# MouseGoggles_HatBrd-1-0.net
KiCad netlist of a schematic drawn in EAGLE
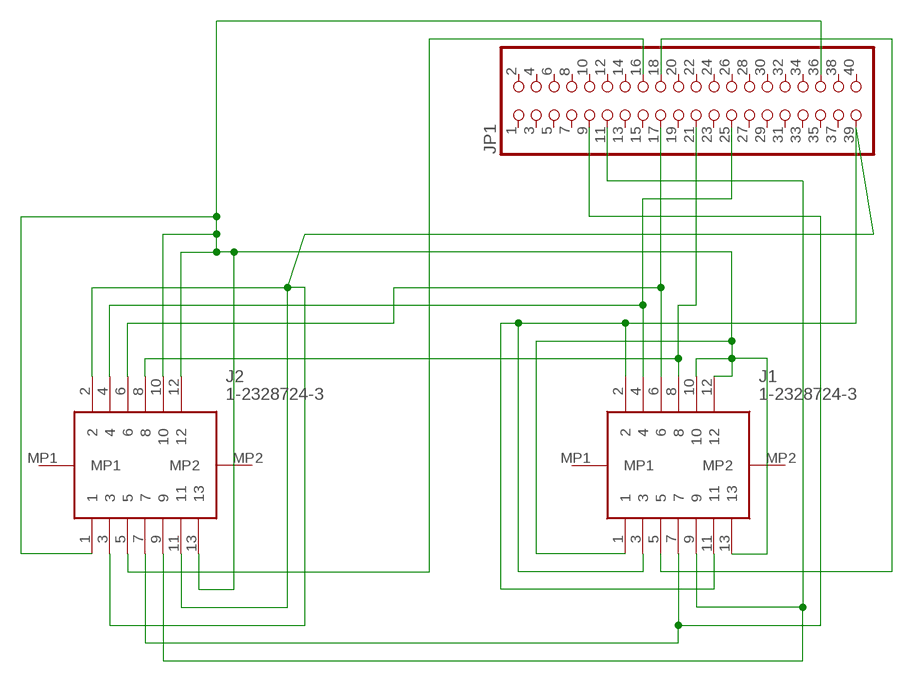
[diagram p0: schematic, sheet 1]

(export (version "E")
  (design (tool "Eeschema 10.0.6"))
  (components
    (comp (ref "J1")
      (value "1-2328724-3")
      (footprint "eagle-import:123287243")
      (fields (field (name "MOUSER_PART_NUMBER") "571-1-2328724-3"))
      (libsource (lib "eagle-import") (part "1-2328724-3"))
    )
    (comp (ref "J2")
      (value "1-2328724-3")
      (footprint "eagle-import:123287243")
      (fields (field (name "MOUSER_PART_NUMBER") "571-1-2328724-3"))
      (libsource (lib "eagle-import") (part "1-2328724-3"))
    )
    (comp (ref "JP1")
      (value "PINHD-2X20-BIG")
      (footprint "eagle-import:2X20-BIG")
      (libsource (lib "eagle-import") (part "PINHD-2X20-BIG"))
    )
  )
  (nets
    (net (code "1") (name "Net-(J1-Pad1)") (class "Default")
      (node (ref "J1") (pin "1") (pinfunction "1_1") (pintype "bidirectional"))
      (node (ref "J1") (pin "10") (pinfunction "10_10") (pintype "bidirectional"))
      (node (ref "J1") (pin "12") (pinfunction "12_12") (pintype "bidirectional"))
      (node (ref "J1") (pin "13") (pinfunction "13_13") (pintype "bidirectional"))
      (node (ref "J2") (pin "1") (pinfunction "1_1") (pintype "bidirectional"))
      (node (ref "J2") (pin "10") (pinfunction "10_10") (pintype "bidirectional"))
      (node (ref "J2") (pin "12") (pinfunction "12_12") (pintype "bidirectional"))
      (node (ref "J2") (pin "13") (pinfunction "13_13") (pintype "bidirectional"))
      (node (ref "JP1") (pin "36") (pinfunction "36_36") (pintype "passive"))
    )
    (net (code "2") (name "Net-(J1-Pad4)") (class "Default")
      (node (ref "J1") (pin "4") (pinfunction "4_4") (pintype "bidirectional"))
      (node (ref "J2") (pin "4") (pinfunction "4_4") (pintype "bidirectional"))
      (node (ref "JP1") (pin "25") (pinfunction "25_25") (pintype "passive"))
    )
    (net (code "3") (name "Net-(J1-Pad5)") (class "Default")
      (node (ref "J1") (pin "5") (pinfunction "5_5") (pintype "bidirectional"))
      (node (ref "JP1") (pin "18") (pinfunction "18_18") (pintype "passive"))
    )
    (net (code "4") (name "Net-(J1-Pad6)") (class "Default")
      (node (ref "J1") (pin "6") (pinfunction "6_6") (pintype "bidirectional"))
      (node (ref "J2") (pin "6") (pinfunction "6_6") (pintype "bidirectional"))
      (node (ref "JP1") (pin "17") (pinfunction "17_17") (pintype "passive"))
    )
    (net (code "5") (name "Net-(J1-Pad7)") (class "Default")
      (node (ref "J1") (pin "7") (pinfunction "7_7") (pintype "bidirectional"))
      (node (ref "J2") (pin "7") (pinfunction "7_7") (pintype "bidirectional"))
      (node (ref "JP1") (pin "9") (pinfunction "9_9") (pintype "passive"))
    )
    (net (code "6") (name "Net-(J1-Pad8)") (class "Default")
      (node (ref "J1") (pin "8") (pinfunction "8_8") (pintype "bidirectional"))
      (node (ref "J2") (pin "8") (pinfunction "8_8") (pintype "bidirectional"))
      (node (ref "JP1") (pin "21") (pinfunction "21_21") (pintype "passive"))
    )
    (net (code "7") (name "Net-(J1-Pad9)") (class "Default")
      (node (ref "J1") (pin "9") (pinfunction "9_9") (pintype "bidirectional"))
      (node (ref "J2") (pin "9") (pinfunction "9_9") (pintype "bidirectional"))
      (node (ref "JP1") (pin "11") (pinfunction "11_11") (pintype "passive"))
    )
    (net (code "8") (name "Net-(J1-Pad11)") (class "Default")
      (node (ref "J1") (pin "11") (pinfunction "11_11") (pintype "bidirectional"))
      (node (ref "J1") (pin "2") (pinfunction "2_2") (pintype "bidirectional"))
      (node (ref "J1") (pin "3") (pinfunction "3_3") (pintype "bidirectional"))
      (node (ref "J2") (pin "11") (pinfunction "11_11") (pintype "bidirectional"))
      (node (ref "J2") (pin "2") (pinfunction "2_2") (pintype "bidirectional"))
      (node (ref "J2") (pin "3") (pinfunction "3_3") (pintype "bidirectional"))
      (node (ref "JP1") (pin "39") (pinfunction "39_39") (pintype "passive"))
    )
    (net (code "9") (name "Net-(J2-Pad5)") (class "Default")
      (node (ref "J2") (pin "5") (pinfunction "5_5") (pintype "bidirectional"))
      (node (ref "JP1") (pin "16") (pinfunction "16_16") (pintype "passive"))
    )
    (net (code "10") (name "unconnected-(J1-PadMP1)") (class "Default")
      (node (ref "J1") (pin "MP1") (pinfunction "MP1_MP1") (pintype "bidirectional"))
    )
    (net (code "11") (name "unconnected-(J1-PadMP2)") (class "Default")
      (node (ref "J1") (pin "MP2") (pinfunction "MP2_MP2") (pintype "bidirectional"))
    )
    (net (code "12") (name "unconnected-(J2-PadMP1)") (class "Default")
      (node (ref "J2") (pin "MP1") (pinfunction "MP1_MP1") (pintype "bidirectional"))
    )
    (net (code "13") (name "unconnected-(J2-PadMP2)") (class "Default")
      (node (ref "J2") (pin "MP2") (pinfunction "MP2_MP2") (pintype "bidirectional"))
    )
    (net (code "14") (name "unconnected-(JP1-Pad1)") (class "Default")
      (node (ref "JP1") (pin "1") (pinfunction "1_1") (pintype "passive"))
    )
    (net (code "15") (name "unconnected-(JP1-Pad2)") (class "Default")
      (node (ref "JP1") (pin "2") (pinfunction "2_2") (pintype "passive"))
    )
    (net (code "16") (name "unconnected-(JP1-Pad3)") (class "Default")
      (node (ref "JP1") (pin "3") (pinfunction "3_3") (pintype "passive"))
    )
    (net (code "17") (name "unconnected-(JP1-Pad4)") (class "Default")
      (node (ref "JP1") (pin "4") (pinfunction "4_4") (pintype "passive"))
    )
    (net (code "18") (name "unconnected-(JP1-Pad5)") (class "Default")
      (node (ref "JP1") (pin "5") (pinfunction "5_5") (pintype "passive"))
    )
    (net (code "19") (name "unconnected-(JP1-Pad6)") (class "Default")
      (node (ref "JP1") (pin "6") (pinfunction "6_6") (pintype "passive"))
    )
    (net (code "20") (name "unconnected-(JP1-Pad7)") (class "Default")
      (node (ref "JP1") (pin "7") (pinfunction "7_7") (pintype "passive"))
    )
    (net (code "21") (name "unconnected-(JP1-Pad8)") (class "Default")
      (node (ref "JP1") (pin "8") (pinfunction "8_8") (pintype "passive"))
    )
    (net (code "22") (name "unconnected-(JP1-Pad10)") (class "Default")
      (node (ref "JP1") (pin "10") (pinfunction "10_10") (pintype "passive"))
    )
    (net (code "23") (name "unconnected-(JP1-Pad12)") (class "Default")
      (node (ref "JP1") (pin "12") (pinfunction "12_12") (pintype "passive"))
    )
    (net (code "24") (name "unconnected-(JP1-Pad13)") (class "Default")
      (node (ref "JP1") (pin "13") (pinfunction "13_13") (pintype "passive"))
    )
    (net (code "25") (name "unconnected-(JP1-Pad14)") (class "Default")
      (node (ref "JP1") (pin "14") (pinfunction "14_14") (pintype "passive"))
    )
    (net (code "26") (name "unconnected-(JP1-Pad15)") (class "Default")
      (node (ref "JP1") (pin "15") (pinfunction "15_15") (pintype "passive"))
    )
    (net (code "27") (name "unconnected-(JP1-Pad19)") (class "Default")
      (node (ref "JP1") (pin "19") (pinfunction "19_19") (pintype "passive"))
    )
    (net (code "28") (name "unconnected-(JP1-Pad20)") (class "Default")
      (node (ref "JP1") (pin "20") (pinfunction "20_20") (pintype "passive"))
    )
    (net (code "29") (name "unconnected-(JP1-Pad22)") (class "Default")
      (node (ref "JP1") (pin "22") (pinfunction "22_22") (pintype "passive"))
    )
    (net (code "30") (name "unconnected-(JP1-Pad23)") (class "Default")
      (node (ref "JP1") (pin "23") (pinfunction "23_23") (pintype "passive"))
    )
    (net (code "31") (name "unconnected-(JP1-Pad24)") (class "Default")
      (node (ref "JP1") (pin "24") (pinfunction "24_24") (pintype "passive"))
    )
    (net (code "32") (name "unconnected-(JP1-Pad26)") (class "Default")
      (node (ref "JP1") (pin "26") (pinfunction "26_26") (pintype "passive"))
    )
    (net (code "33") (name "unconnected-(JP1-Pad27)") (class "Default")
      (node (ref "JP1") (pin "27") (pinfunction "27_27") (pintype "passive"))
    )
    (net (code "34") (name "unconnected-(JP1-Pad28)") (class "Default")
      (node (ref "JP1") (pin "28") (pinfunction "28_28") (pintype "passive"))
    )
    (net (code "35") (name "unconnected-(JP1-Pad29)") (class "Default")
      (node (ref "JP1") (pin "29") (pinfunction "29_29") (pintype "passive"))
    )
    (net (code "36") (name "unconnected-(JP1-Pad30)") (class "Default")
      (node (ref "JP1") (pin "30") (pinfunction "30_30") (pintype "passive"))
    )
    (net (code "37") (name "unconnected-(JP1-Pad31)") (class "Default")
      (node (ref "JP1") (pin "31") (pinfunction "31_31") (pintype "passive"))
    )
    (net (code "38") (name "unconnected-(JP1-Pad32)") (class "Default")
      (node (ref "JP1") (pin "32") (pinfunction "32_32") (pintype "passive"))
    )
    (net (code "39") (name "unconnected-(JP1-Pad33)") (class "Default")
      (node (ref "JP1") (pin "33") (pinfunction "33_33") (pintype "passive"))
    )
    (net (code "40") (name "unconnected-(JP1-Pad34)") (class "Default")
      (node (ref "JP1") (pin "34") (pinfunction "34_34") (pintype "passive"))
    )
    (net (code "41") (name "unconnected-(JP1-Pad35)") (class "Default")
      (node (ref "JP1") (pin "35") (pinfunction "35_35") (pintype "passive"))
    )
    (net (code "42") (name "unconnected-(JP1-Pad37)") (class "Default")
      (node (ref "JP1") (pin "37") (pinfunction "37_37") (pintype "passive"))
    )
    (net (code "43") (name "unconnected-(JP1-Pad38)") (class "Default")
      (node (ref "JP1") (pin "38") (pinfunction "38_38") (pintype "passive"))
    )
    (net (code "44") (name "unconnected-(JP1-Pad40)") (class "Default")
      (node (ref "JP1") (pin "40") (pinfunction "40_40") (pintype "passive"))
    )
  )
)
